# Ground_Station_Board.net
KiCad netlist of a schematic drawn in EAGLE
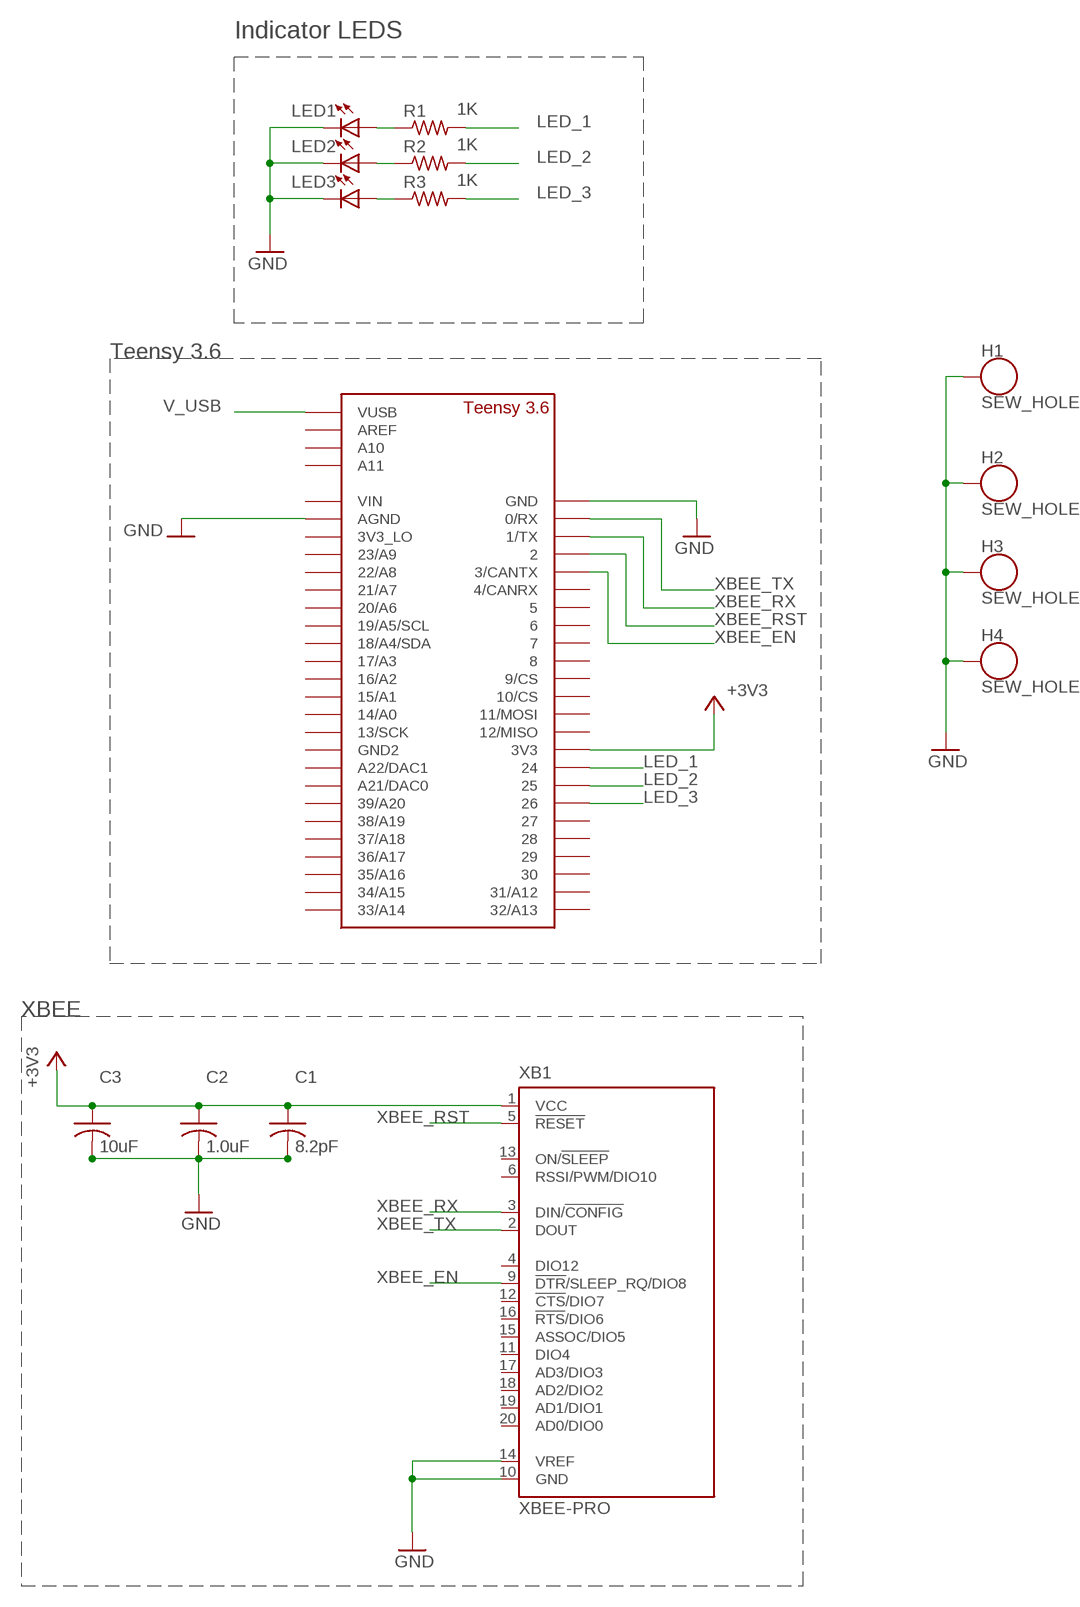
[diagram p0: schematic, sheet 1]

(export (version "E")
  (design (tool "Eeschema 10.0.6"))
  (components
    (comp (ref "C1")
      (value "8.2pF")
      (footprint "eagle-import:C025-024X044")
      (libsource (lib "eagle-import") (part "C-US025-024X044"))
    )
    (comp (ref "C2")
      (value "1.0uF")
      (footprint "eagle-import:C025-024X044")
      (libsource (lib "eagle-import") (part "C-US025-024X044"))
    )
    (comp (ref "C3")
      (value "10uF")
      (footprint "eagle-import:C025-024X044")
      (libsource (lib "eagle-import") (part "C-US025-024X044"))
    )
    (comp (ref "H1")
      (value "SEW_HOLE")
      (footprint "eagle-import:SIMPLE_HOLE")
      (libsource (lib "eagle-import") (part "SEW_HOLE"))
    )
    (comp (ref "H2")
      (value "SEW_HOLE")
      (footprint "eagle-import:SIMPLE_HOLE")
      (libsource (lib "eagle-import") (part "SEW_HOLE"))
    )
    (comp (ref "H3")
      (value "SEW_HOLE")
      (footprint "eagle-import:SIMPLE_HOLE")
      (libsource (lib "eagle-import") (part "SEW_HOLE"))
    )
    (comp (ref "H4")
      (value "SEW_HOLE")
      (footprint "eagle-import:SIMPLE_HOLE")
      (libsource (lib "eagle-import") (part "SEW_HOLE"))
    )
    (comp (ref "LED1")
      (value "LED5MM")
      (footprint "eagle-import:LED5MM")
      (libsource (lib "eagle-import") (part "LED5MM"))
    )
    (comp (ref "LED2")
      (value "LED5MM")
      (footprint "eagle-import:LED5MM")
      (libsource (lib "eagle-import") (part "LED5MM"))
    )
    (comp (ref "LED3")
      (value "LED5MM")
      (footprint "eagle-import:LED5MM")
      (libsource (lib "eagle-import") (part "LED5MM"))
    )
    (comp (ref "R1")
      (value "1K")
      (footprint "eagle-import:0207_7")
      (libsource (lib "eagle-import") (part "R-US_0207/7"))
    )
    (comp (ref "R2")
      (value "1K")
      (footprint "eagle-import:0207_7")
      (libsource (lib "eagle-import") (part "R-US_0207/7"))
    )
    (comp (ref "R3")
      (value "1K")
      (footprint "eagle-import:0207_7")
      (libsource (lib "eagle-import") (part "R-US_0207/7"))
    )
    (comp (ref "U$2")
      (value "TEENSY_3.5/3.6_BASIC")
      (footprint "eagle-import:TEENSY_3.5_3.6_BASIC")
      (libsource (lib "eagle-import") (part "TEENSY_3.5/3.6_BASIC"))
    )
    (comp (ref "XB1")
      (value "XBEE-PRO")
      (footprint "eagle-import:XBEE-PRO")
      (fields (field (name "MPN") "XBP24-AWI-001"))
      (libsource (lib "eagle-import") (part "XBEE-PRO"))
    )
  )
  (nets
    (net (code "1") (name "+3V3") (class "Default")
      (node (ref "C1") (pin "1") (pinfunction "1_1") (pintype "passive"))
      (node (ref "C2") (pin "1") (pinfunction "1_1") (pintype "passive"))
      (node (ref "C3") (pin "1") (pinfunction "1_1") (pintype "passive"))
      (node (ref "U$2") (pin "3V3") (pinfunction "3V3_3V3") (pintype "bidirectional"))
      (node (ref "XB1") (pin "1") (pinfunction "VCC_1") (pintype "power_in"))
    )
    (net (code "2") (name "/LED_1") (class "Default")
      (node (ref "R1") (pin "2") (pinfunction "2_2") (pintype "passive"))
      (node (ref "U$2") (pin "24") (pinfunction "24_24") (pintype "bidirectional"))
    )
    (net (code "3") (name "/LED_2") (class "Default")
      (node (ref "R2") (pin "2") (pinfunction "2_2") (pintype "passive"))
      (node (ref "U$2") (pin "25") (pinfunction "25_25") (pintype "bidirectional"))
    )
    (net (code "4") (name "/LED_3") (class "Default")
      (node (ref "R3") (pin "2") (pinfunction "2_2") (pintype "passive"))
      (node (ref "U$2") (pin "26") (pinfunction "26_26") (pintype "bidirectional"))
    )
    (net (code "5") (name "/V_USB") (class "Default")
      (node (ref "U$2") (pin "VUSB") (pinfunction "VUSB_VUSB") (pintype "bidirectional"))
    )
    (net (code "6") (name "/XBEE_EN") (class "Default")
      (node (ref "U$2") (pin "3/CANTX") (pinfunction "3/CANTX_3/CANTX") (pintype "bidirectional"))
      (node (ref "XB1") (pin "9") (pinfunction "~{DTR}/SLEEP_RQ/DIO8_9") (pintype "bidirectional"))
    )
    (net (code "7") (name "/XBEE_RST") (class "Default")
      (node (ref "U$2") (pin "2") (pinfunction "2_2") (pintype "bidirectional"))
      (node (ref "XB1") (pin "5") (pinfunction "~{RESET}_5") (pintype "input"))
    )
    (net (code "8") (name "/XBEE_RX") (class "Default")
      (node (ref "U$2") (pin "1/TX") (pinfunction "1/TX_1/TX") (pintype "bidirectional"))
      (node (ref "XB1") (pin "3") (pinfunction "DIN/~{CONFIG}_3") (pintype "input"))
    )
    (net (code "9") (name "/XBEE_TX") (class "Default")
      (node (ref "U$2") (pin "0/RX") (pinfunction "0/RX_0/RX") (pintype "bidirectional"))
      (node (ref "XB1") (pin "2") (pinfunction "DOUT_2") (pintype "output"))
    )
    (net (code "10") (name "GND") (class "Default")
      (node (ref "C1") (pin "2") (pinfunction "2_2") (pintype "passive"))
      (node (ref "C2") (pin "2") (pinfunction "2_2") (pintype "passive"))
      (node (ref "C3") (pin "2") (pinfunction "2_2") (pintype "passive"))
      (node (ref "H1") (pin "P$1") (pinfunction "P$1_P$1") (pintype "bidirectional"))
      (node (ref "H2") (pin "P$1") (pinfunction "P$1_P$1") (pintype "bidirectional"))
      (node (ref "H3") (pin "P$1") (pinfunction "P$1_P$1") (pintype "bidirectional"))
      (node (ref "H4") (pin "P$1") (pinfunction "P$1_P$1") (pintype "bidirectional"))
      (node (ref "LED1") (pin "K") (pinfunction "C_K") (pintype "passive"))
      (node (ref "LED2") (pin "K") (pinfunction "C_K") (pintype "passive"))
      (node (ref "LED3") (pin "K") (pinfunction "C_K") (pintype "passive"))
      (node (ref "U$2") (pin "AGND") (pinfunction "AGND_AGND") (pintype "bidirectional"))
      (node (ref "U$2") (pin "GND") (pinfunction "GND_GND") (pintype "bidirectional"))
      (node (ref "XB1") (pin "10") (pinfunction "GND_10") (pintype "power_in"))
      (node (ref "XB1") (pin "14") (pinfunction "VREF_14") (pintype "input"))
    )
    (net (code "11") (name "Net-(LED1-PadA)") (class "Default")
      (node (ref "LED1") (pin "A") (pinfunction "A_A") (pintype "passive"))
      (node (ref "R1") (pin "1") (pinfunction "1_1") (pintype "passive"))
    )
    (net (code "12") (name "Net-(LED2-PadA)") (class "Default")
      (node (ref "LED2") (pin "A") (pinfunction "A_A") (pintype "passive"))
      (node (ref "R2") (pin "1") (pinfunction "1_1") (pintype "passive"))
    )
    (net (code "13") (name "Net-(LED3-PadA)") (class "Default")
      (node (ref "LED3") (pin "A") (pinfunction "A_A") (pintype "passive"))
      (node (ref "R3") (pin "1") (pinfunction "1_1") (pintype "passive"))
    )
    (net (code "14") (name "unconnected-(U$2-A21{slash}DAC0-Pad21{slash}DAC0)") (class "Default")
      (node (ref "U$2") (pin "21/DAC0") (pinfunction "A21/DAC0_21/DAC0") (pintype "bidirectional"))
    )
    (net (code "15") (name "unconnected-(U$2-Pad3V3_LO)") (class "Default")
      (node (ref "U$2") (pin "3V3_LO") (pinfunction "3V3_LO_3V3_LO") (pintype "bidirectional"))
    )
    (net (code "16") (name "unconnected-(U$2-Pad4{slash}CANRX)") (class "Default")
      (node (ref "U$2") (pin "4/CANRX") (pinfunction "4/CANRX_4/CANRX") (pintype "bidirectional"))
    )
    (net (code "17") (name "unconnected-(U$2-Pad5)") (class "Default")
      (node (ref "U$2") (pin "5") (pinfunction "5_5") (pintype "bidirectional"))
    )
    (net (code "18") (name "unconnected-(U$2-Pad6)") (class "Default")
      (node (ref "U$2") (pin "6") (pinfunction "6_6") (pintype "bidirectional"))
    )
    (net (code "19") (name "unconnected-(U$2-Pad7)") (class "Default")
      (node (ref "U$2") (pin "7") (pinfunction "7_7") (pintype "bidirectional"))
    )
    (net (code "20") (name "unconnected-(U$2-Pad8)") (class "Default")
      (node (ref "U$2") (pin "8") (pinfunction "8_8") (pintype "bidirectional"))
    )
    (net (code "21") (name "unconnected-(U$2-Pad9{slash}CS)") (class "Default")
      (node (ref "U$2") (pin "9/CS") (pinfunction "9/CS_9/CS") (pintype "bidirectional"))
    )
    (net (code "22") (name "unconnected-(U$2-Pad10{slash}CS)") (class "Default")
      (node (ref "U$2") (pin "10/CS") (pinfunction "10/CS_10/CS") (pintype "bidirectional"))
    )
    (net (code "23") (name "unconnected-(U$2-Pad11{slash}MOSI)") (class "Default")
      (node (ref "U$2") (pin "11/MOSI") (pinfunction "11/MOSI_11/MOSI") (pintype "bidirectional"))
    )
    (net (code "24") (name "unconnected-(U$2-Pad12{slash}MISO)") (class "Default")
      (node (ref "U$2") (pin "12/MISO") (pinfunction "12/MISO_12/MISO") (pintype "bidirectional"))
    )
    (net (code "25") (name "unconnected-(U$2-Pad13{slash}SCK)") (class "Default")
      (node (ref "U$2") (pin "13/SCK") (pinfunction "13/SCK_13/SCK") (pintype "bidirectional"))
    )
    (net (code "26") (name "unconnected-(U$2-Pad14{slash}A0)") (class "Default")
      (node (ref "U$2") (pin "14/A0") (pinfunction "14/A0_14/A0") (pintype "bidirectional"))
    )
    (net (code "27") (name "unconnected-(U$2-Pad15{slash}A1)") (class "Default")
      (node (ref "U$2") (pin "15/A1") (pinfunction "15/A1_15/A1") (pintype "bidirectional"))
    )
    (net (code "28") (name "unconnected-(U$2-Pad16{slash}A2)") (class "Default")
      (node (ref "U$2") (pin "16/A2") (pinfunction "16/A2_16/A2") (pintype "bidirectional"))
    )
    (net (code "29") (name "unconnected-(U$2-Pad17{slash}A3)") (class "Default")
      (node (ref "U$2") (pin "17/A3") (pinfunction "17/A3_17/A3") (pintype "bidirectional"))
    )
    (net (code "30") (name "unconnected-(U$2-Pad18{slash}A4{slash}SDA)") (class "Default")
      (node (ref "U$2") (pin "18/A4/SDA") (pinfunction "18/A4/SDA_18/A4/SDA") (pintype "bidirectional"))
    )
    (net (code "31") (name "unconnected-(U$2-Pad19{slash}A5{slash}SCL)") (class "Default")
      (node (ref "U$2") (pin "19/A5/SCL") (pinfunction "19/A5/SCL_19/A5/SCL") (pintype "bidirectional"))
    )
    (net (code "32") (name "unconnected-(U$2-Pad20{slash}A6)") (class "Default")
      (node (ref "U$2") (pin "20/A6") (pinfunction "20/A6_20/A6") (pintype "bidirectional"))
    )
    (net (code "33") (name "unconnected-(U$2-Pad21{slash}A7)") (class "Default")
      (node (ref "U$2") (pin "21/A7") (pinfunction "21/A7_21/A7") (pintype "bidirectional"))
    )
    (net (code "34") (name "unconnected-(U$2-Pad22{slash}A8)") (class "Default")
      (node (ref "U$2") (pin "22/A8") (pinfunction "22/A8_22/A8") (pintype "bidirectional"))
    )
    (net (code "35") (name "unconnected-(U$2-Pad23{slash}A9)") (class "Default")
      (node (ref "U$2") (pin "23/A9") (pinfunction "23/A9_23/A9") (pintype "bidirectional"))
    )
    (net (code "36") (name "unconnected-(U$2-Pad27)") (class "Default")
      (node (ref "U$2") (pin "27") (pinfunction "27_27") (pintype "bidirectional"))
    )
    (net (code "37") (name "unconnected-(U$2-Pad28)") (class "Default")
      (node (ref "U$2") (pin "28") (pinfunction "28_28") (pintype "bidirectional"))
    )
    (net (code "38") (name "unconnected-(U$2-Pad29)") (class "Default")
      (node (ref "U$2") (pin "29") (pinfunction "29_29") (pintype "bidirectional"))
    )
    (net (code "39") (name "unconnected-(U$2-Pad30)") (class "Default")
      (node (ref "U$2") (pin "30") (pinfunction "30_30") (pintype "bidirectional"))
    )
    (net (code "40") (name "unconnected-(U$2-Pad31{slash}A12)") (class "Default")
      (node (ref "U$2") (pin "31/A12") (pinfunction "31/A12_31/A12") (pintype "bidirectional"))
    )
    (net (code "41") (name "unconnected-(U$2-Pad32{slash}A13)") (class "Default")
      (node (ref "U$2") (pin "32/A13") (pinfunction "32/A13_32/A13") (pintype "bidirectional"))
    )
    (net (code "42") (name "unconnected-(U$2-Pad33{slash}A14)") (class "Default")
      (node (ref "U$2") (pin "33/A14") (pinfunction "33/A14_33/A14") (pintype "bidirectional"))
    )
    (net (code "43") (name "unconnected-(U$2-Pad34{slash}A15)") (class "Default")
      (node (ref "U$2") (pin "34/A15") (pinfunction "34/A15_34/A15") (pintype "bidirectional"))
    )
    (net (code "44") (name "unconnected-(U$2-Pad35{slash}A16)") (class "Default")
      (node (ref "U$2") (pin "35/A16") (pinfunction "35/A16_35/A16") (pintype "bidirectional"))
    )
    (net (code "45") (name "unconnected-(U$2-Pad36{slash}A17)") (class "Default")
      (node (ref "U$2") (pin "36/A17") (pinfunction "36/A17_36/A17") (pintype "bidirectional"))
    )
    (net (code "46") (name "unconnected-(U$2-Pad37{slash}A18)") (class "Default")
      (node (ref "U$2") (pin "37/A18") (pinfunction "37/A18_37/A18") (pintype "bidirectional"))
    )
    (net (code "47") (name "unconnected-(U$2-Pad38{slash}A19)") (class "Default")
      (node (ref "U$2") (pin "38/A19") (pinfunction "38/A19_38/A19") (pintype "bidirectional"))
    )
    (net (code "48") (name "unconnected-(U$2-Pad39{slash}A20)") (class "Default")
      (node (ref "U$2") (pin "39/A20") (pinfunction "39/A20_39/A20") (pintype "bidirectional"))
    )
    (net (code "49") (name "unconnected-(U$2-PadA10)") (class "Default")
      (node (ref "U$2") (pin "A10") (pinfunction "A10_A10") (pintype "bidirectional"))
    )
    (net (code "50") (name "unconnected-(U$2-PadA11)") (class "Default")
      (node (ref "U$2") (pin "A11") (pinfunction "A11_A11") (pintype "bidirectional"))
    )
    (net (code "51") (name "unconnected-(U$2-PadA22{slash}DAC1)") (class "Default")
      (node (ref "U$2") (pin "A22/DAC1") (pinfunction "A22/DAC1_A22/DAC1") (pintype "bidirectional"))
    )
    (net (code "52") (name "unconnected-(U$2-PadAREF)") (class "Default")
      (node (ref "U$2") (pin "AREF") (pinfunction "AREF_AREF") (pintype "bidirectional"))
    )
    (net (code "53") (name "unconnected-(U$2-PadGND2)") (class "Default")
      (node (ref "U$2") (pin "GND2") (pinfunction "GND2_GND2") (pintype "bidirectional"))
    )
    (net (code "54") (name "unconnected-(U$2-PadVIN)") (class "Default")
      (node (ref "U$2") (pin "VIN") (pinfunction "VIN_VIN") (pintype "bidirectional"))
    )
    (net (code "55") (name "unconnected-(XB1-AD0{slash}DIO0-Pad20)") (class "Default")
      (node (ref "XB1") (pin "20") (pinfunction "AD0/DIO0_20") (pintype "bidirectional"))
    )
    (net (code "56") (name "unconnected-(XB1-AD1{slash}DIO1-Pad19)") (class "Default")
      (node (ref "XB1") (pin "19") (pinfunction "AD1/DIO1_19") (pintype "bidirectional"))
    )
    (net (code "57") (name "unconnected-(XB1-AD2{slash}DIO2-Pad18)") (class "Default")
      (node (ref "XB1") (pin "18") (pinfunction "AD2/DIO2_18") (pintype "bidirectional"))
    )
    (net (code "58") (name "unconnected-(XB1-AD3{slash}DIO3-Pad17)") (class "Default")
      (node (ref "XB1") (pin "17") (pinfunction "AD3/DIO3_17") (pintype "bidirectional"))
    )
    (net (code "59") (name "unconnected-(XB1-ASSOC{slash}DIO5-Pad15)") (class "Default")
      (node (ref "XB1") (pin "15") (pinfunction "ASSOC/DIO5_15") (pintype "bidirectional"))
    )
    (net (code "60") (name "unconnected-(XB1-DIO4-Pad11)") (class "Default")
      (node (ref "XB1") (pin "11") (pinfunction "DIO4_11") (pintype "bidirectional"))
    )
    (net (code "61") (name "unconnected-(XB1-DIO12-Pad4)") (class "Default")
      (node (ref "XB1") (pin "4") (pinfunction "DIO12_4") (pintype "bidirectional"))
    )
    (net (code "62") (name "unconnected-(XB1-ON{slash}~{SLEEP}-Pad13)") (class "Default")
      (node (ref "XB1") (pin "13") (pinfunction "ON/~{SLEEP}_13") (pintype "output"))
    )
    (net (code "63") (name "unconnected-(XB1-RSSI{slash}PWM{slash}DIO10-Pad6)") (class "Default")
      (node (ref "XB1") (pin "6") (pinfunction "RSSI/PWM/DIO10_6") (pintype "output"))
    )
    (net (code "64") (name "unconnected-(XB1-~{CTS}{slash}DIO7-Pad12)") (class "Default")
      (node (ref "XB1") (pin "12") (pinfunction "~{CTS}/DIO7_12") (pintype "bidirectional"))
    )
    (net (code "65") (name "unconnected-(XB1-~{RTS}{slash}DIO6-Pad16)") (class "Default")
      (node (ref "XB1") (pin "16") (pinfunction "~{RTS}/DIO6_16") (pintype "bidirectional"))
    )
  )
)
